# Tomashevich.net
KiCad netlist of a schematic drawn in Altium Designer
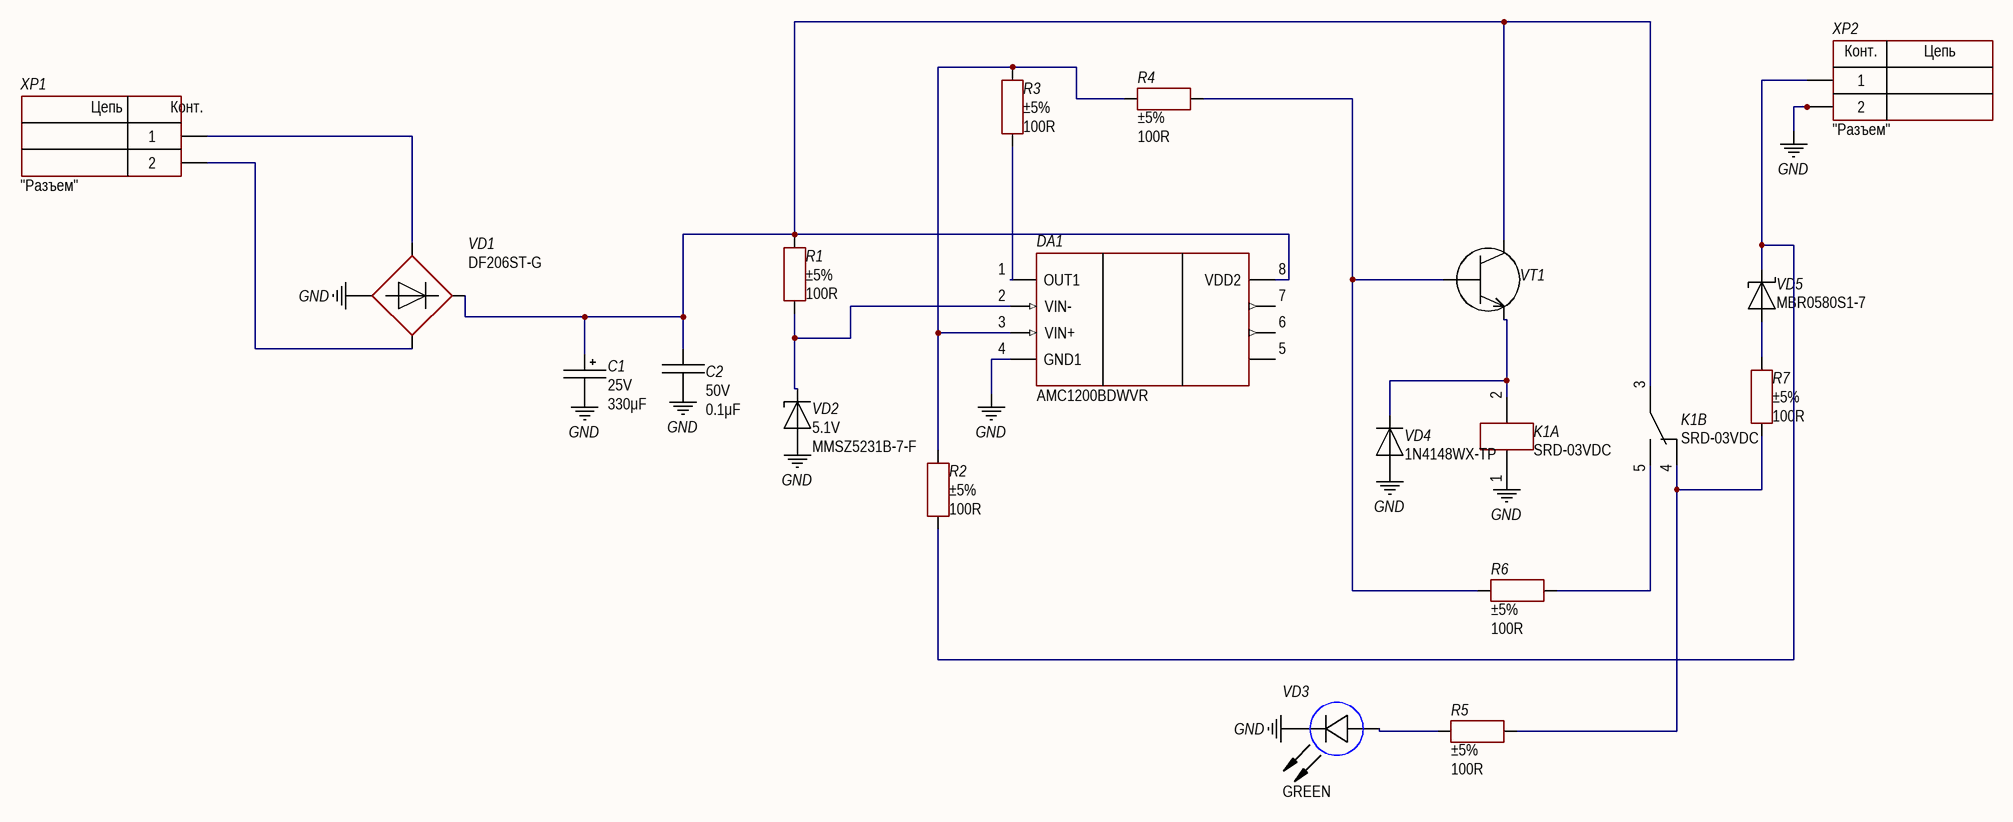
[diagram p0: Tomashevich.SchDoc]

(export (version "E")
  (design (tool "Eeschema 10.0.6"))
  (components
    (comp (ref "C1")
      (value "330μF")
      (footprint "CAP: D6.3C2.5H11")
      (fields
        (field (name "MANUFACTURER") "Wurth")
        (field (name "PARTNUMBER") "860080475013")
        (field (name "VALUEMANUFACTURERPARTNUMBER") "Aluminium capacitor, 330μF, 25V, ±20%, 54mOhm, 14x10x5 mm, -55...+105°C")
        (field (name "VOLTAGE") "25V")
      )
      (libsource (lib "capacitor") (part "Aluminium"))
    )
    (comp (ref "C2")
      (value "0.1μF")
      (footprint "CAP: 1206")
      (fields
        (field (name "MANUFACTURER") "Yageo")
        (field (name "PARTNUMBER") "CC1206KRX7R9BB104")
        (field (name "VALUEMANUFACTURERPARTNUMBER") "Ceramic capacitor, 0.1μF, X7R, ±10%, 50V, 1206, -55...+125°C")
        (field (name "VOLTAGE") "50V")
      )
      (libsource (lib "capacitor") (part "Ceramic_1206"))
    )
    (comp (ref "DA1")
      (value "~")
      (footprint "8-SOIC-W")
      (description "Isolator amplifier")
      (fields
        (field (name "MANUFACTURER") "Texas Instruments")
        (field (name "VALUEMANUFACTURERPARTNUMBER") "IC isolator amplifier, Differential, 100 kHz, 2.7...5.5V, -40...+105°C, 8-SOIC")
        (field (name "PARTNUMBER") "AMC1200BDWVR")
      )
      (libsource (lib "ic-amplifier") (part "AMC1200BDWVR"))
    )
    (comp (ref "K1")
      (value "~")
      (footprint "REL: SRD-03VDC")
      (fields
        (field (name "MANUFACTURER") "Ningbo Songle")
        (field (name "VALUEMANUFACTURERPARTNUMBER") "Electromechanics relay, 3VDC, 250VAC, 10A, 1NO, -40...+85°C")
        (field (name "PARTNUMBER") "SRD-03VDC")
      )
      (libsource (lib "") (part "Relay_SRD-03VDC_1"))
    )
    (comp (ref "R1")
      (value "100R")
      (footprint "RES: 1206")
      (fields
        (field (name "MANUFACTURER") "Yageo")
        (field (name "PARTNUMBER") "RC1206JR-07100RL")
        (field (name "VALUEMANUFACTURERPARTNUMBER") "Resistor film, 100R, ±5%, 1206, 0.25W, -55...+125°C")
        (field (name "TOLERANCE") "±5%")
      )
      (libsource (lib "resistor") (part "Resistor_1206"))
    )
    (comp (ref "R2")
      (value "100R")
      (footprint "RES: 1206")
      (fields
        (field (name "MANUFACTURER") "Yageo")
        (field (name "PARTNUMBER") "RC1206JR-07100RL")
        (field (name "VALUEMANUFACTURERPARTNUMBER") "Resistor film, 100R, ±5%, 1206, 0.25W, -55...+125°C")
        (field (name "TOLERANCE") "±5%")
      )
      (libsource (lib "resistor") (part "Resistor_1206"))
    )
    (comp (ref "R3")
      (value "100R")
      (footprint "RES: 1206")
      (fields
        (field (name "MANUFACTURER") "Yageo")
        (field (name "PARTNUMBER") "RC1206JR-07100RL")
        (field (name "VALUEMANUFACTURERPARTNUMBER") "Resistor film, 100R, ±5%, 1206, 0.25W, -55...+125°C")
        (field (name "TOLERANCE") "±5%")
      )
      (libsource (lib "resistor") (part "Resistor_1206"))
    )
    (comp (ref "R4")
      (value "100R")
      (footprint "RES: 1206")
      (fields
        (field (name "MANUFACTURER") "Yageo")
        (field (name "PARTNUMBER") "RC1206JR-07100RL")
        (field (name "VALUEMANUFACTURERPARTNUMBER") "Resistor film, 100R, ±5%, 1206, 0.25W, -55...+125°C")
        (field (name "TOLERANCE") "±5%")
      )
      (libsource (lib "") (part "Resistor_1206_2"))
    )
    (comp (ref "R5")
      (value "100R")
      (footprint "RES: 1206")
      (fields
        (field (name "MANUFACTURER") "Yageo")
        (field (name "PARTNUMBER") "RC1206JR-07100RL")
        (field (name "VALUEMANUFACTURERPARTNUMBER") "Resistor film, 100R, ±5%, 1206, 0.25W, -55...+125°C")
        (field (name "TOLERANCE") "±5%")
      )
      (libsource (lib "") (part "Resistor_1206_1"))
    )
    (comp (ref "R6")
      (value "100R")
      (footprint "RES: 1206")
      (fields
        (field (name "MANUFACTURER") "Yageo")
        (field (name "PARTNUMBER") "RC1206JR-07100RL")
        (field (name "VALUEMANUFACTURERPARTNUMBER") "Resistor film, 100R, ±5%, 1206, 0.25W, -55...+125°C")
        (field (name "TOLERANCE") "±5%")
      )
      (libsource (lib "") (part "Resistor_1206_1"))
    )
    (comp (ref "R7")
      (value "100R")
      (footprint "RES: 1206")
      (fields
        (field (name "MANUFACTURER") "Yageo")
        (field (name "PARTNUMBER") "RC1206JR-07100RL")
        (field (name "VALUEMANUFACTURERPARTNUMBER") "Resistor film, 100R, ±5%, 1206, 0.25W, -55...+125°C")
        (field (name "TOLERANCE") "±5%")
      )
      (libsource (lib "resistor") (part "Resistor_1206"))
    )
    (comp (ref "VD1")
      (value "~")
      (footprint "DIODE: CD-MBL2")
      (fields
        (field (name "MANUFACTURER") "Comchip Technology")
        (field (name "VALUEMANUFACTURERPARTNUMBER") "Single phase rectifier, 600V, 2A, 1.1V, 4-SMD, -55...+150°C")
        (field (name "VOLTAGE") "600V")
        (field (name "PARTNUMBER") "DF206ST-G")
      )
      (libsource (lib "diode") (part "1PH rectifier"))
    )
    (comp (ref "VD2")
      (value "~")
      (footprint "DIODE: SMA")
      (fields
        (field (name "MANUFACTURER") "Diodes Incorporated")
        (field (name "VALUEMANUFACTURERPARTNUMBER") "Zener diode, 5.1V, 500mW, 0.9V, 17Ohm, SOD-123, -55...+150°C")
        (field (name "VOLTAGE") "5.1V")
        (field (name "PARTNUMBER") "MMSZ5231B-7-F")
      )
      (libsource (lib "diode") (part "Zener_single"))
    )
    (comp (ref "VD3")
      (value "~")
      (footprint "LED: 1206G")
      (fields
        (field (name "VALUEMANUFACTURERPARTNUMBER") "LED, Green, *, *, *, -55...+150°C")
        (field (name "COLOR") "GREEN")
      )
      (libsource (lib "diode") (part "LED_single"))
    )
    (comp (ref "VD4")
      (value "~")
      (footprint "DIODE: SMA")
      (fields
        (field (name "MANUFACTURER") "Micro Commercial")
        (field (name "VALUEMANUFACTURERPARTNUMBER") "Single diode, 75V, 150mA, 1V, 4ns, SOD-323, -55...+150°C")
        (field (name "VOLTAGE") "75V")
        (field (name "PARTNUMBER") "1N4148WX-TP")
      )
      (libsource (lib "diode") (part "Diode_single"))
    )
    (comp (ref "VD5")
      (value "~")
      (footprint "DIODE: SMA")
      (fields
        (field (name "MANUFACTURER") "Diodes Incorporated")
        (field (name "VALUEMANUFACTURERPARTNUMBER") "Schottky diode, 80V, 500mA, 1V, 15pF, SOD-123, -55...+150°C")
        (field (name "VOLTAGE") "80V")
        (field (name "PARTNUMBER") "MBR0580S1-7")
      )
      (libsource (lib "diode") (part "Schottky_single"))
    )
    (comp (ref "VT1")
      (value "transistor")
      (footprint "TO247")
      (libsource (lib "Schlib1") (part "transistor"))
    )
    (comp (ref "XP1")
      (value "~")
      (footprint "CON: DG350-3.5-02P")
      (fields
        (field (name "MANUFACTURER") "Degson")
        (field (name "VALUEMANUFACTURERPARTNUMBER") "Terminal connector, 2pin, 3.5mm, 300VAC, 10A")
        (field (name "PARTNUMBER") "DG350-3.5-02P-14")
        (field (name "COMMENTTEXT") "\"Разъем\"")
      )
      (libsource (lib "connector") (part "Connector_terminal_2pin"))
    )
    (comp (ref "XP2")
      (value "~")
      (footprint "CON: DG350-3.5-02P")
      (fields
        (field (name "MANUFACTURER") "Degson")
        (field (name "VALUEMANUFACTURERPARTNUMBER") "Terminal connector, 2pin, 3.5mm, 300VAC, 10A")
        (field (name "PARTNUMBER") "DG350-3.5-02P-14")
        (field (name "COMMENTTEXT") "\"Разъем\"")
      )
      (libsource (lib "") (part "Connector_terminal_2pin_1"))
    )
  )
  (nets
    (net (code "1") (name "GND") (class "Default")
      (node (ref "C1") (pin "2") (pinfunction "2_2") (pintype "passive"))
      (node (ref "C2") (pin "1") (pinfunction "1_1") (pintype "passive"))
      (node (ref "DA1") (pin "4") (pinfunction "GND1_4") (pintype "power_in"))
      (node (ref "K1") (pin "1") (pinfunction "1_1") (pintype "passive"))
      (node (ref "VD1") (pin "1") (pinfunction "1_1") (pintype "passive"))
      (node (ref "VD2") (pin "1") (pinfunction "A_1") (pintype "passive"))
      (node (ref "VD3") (pin "2") (pinfunction "C_2") (pintype "passive"))
      (node (ref "VD4") (pin "1") (pinfunction "1_1") (pintype "passive"))
      (node (ref "XP2") (pin "2") (pinfunction "2_2") (pintype "passive"))
    )
    (net (code "2") (name "Net-(DA1-OUT1)") (class "Default")
      (node (ref "DA1") (pin "1") (pinfunction "OUT1_1") (pintype "power_in"))
      (node (ref "R3") (pin "1") (pinfunction "1_1") (pintype "passive"))
    )
    (net (code "3") (name "Net-(DA1-VDD2)") (class "Default")
      (node (ref "C1") (pin "1") (pinfunction "1_1") (pintype "passive"))
      (node (ref "C2") (pin "2") (pinfunction "2_2") (pintype "passive"))
      (node (ref "DA1") (pin "8") (pinfunction "VDD2_8") (pintype "power_in"))
      (node (ref "K1") (pin "3") (pinfunction "3_3") (pintype "passive"))
      (node (ref "R1") (pin "2") (pinfunction "2_2") (pintype "passive"))
      (node (ref "VD1") (pin "3") (pinfunction "3_3") (pintype "passive"))
      (node (ref "VT1") (pin "3") (pinfunction "3_3") (pintype "passive"))
    )
    (net (code "4") (name "Net-(DA1-VIN+)") (class "Default")
      (node (ref "DA1") (pin "3") (pinfunction "VIN+_3") (pintype "input"))
      (node (ref "R2") (pin "2") (pinfunction "2_2") (pintype "passive"))
      (node (ref "R3") (pin "2") (pinfunction "2_2") (pintype "passive"))
      (node (ref "R4") (pin "2") (pinfunction "2_2") (pintype "passive"))
    )
    (net (code "5") (name "Net-(DA1-VIN-)") (class "Default")
      (node (ref "DA1") (pin "2") (pinfunction "VIN-_2") (pintype "input"))
      (node (ref "R1") (pin "1") (pinfunction "1_1") (pintype "passive"))
      (node (ref "VD2") (pin "2") (pinfunction "C_2") (pintype "passive"))
    )
    (net (code "6") (name "Net-(K1-Pad2)") (class "Default")
      (node (ref "K1") (pin "2") (pinfunction "2_2") (pintype "passive"))
      (node (ref "VD4") (pin "2") (pinfunction "2_2") (pintype "passive"))
      (node (ref "VT1") (pin "2") (pinfunction "2_2") (pintype "passive"))
    )
    (net (code "7") (name "Net-(K1-Pad4)") (class "Default")
      (node (ref "K1") (pin "4") (pinfunction "4_4") (pintype "passive"))
      (node (ref "R5") (pin "1") (pinfunction "1_1") (pintype "passive"))
      (node (ref "R7") (pin "1") (pinfunction "1_1") (pintype "passive"))
    )
    (net (code "8") (name "Net-(K1-Pad5)") (class "Default")
      (node (ref "K1") (pin "5") (pinfunction "5_5") (pintype "passive"))
      (node (ref "R6") (pin "1") (pinfunction "1_1") (pintype "passive"))
    )
    (net (code "9") (name "Net-(R2-Pad1)") (class "Default")
      (node (ref "R2") (pin "1") (pinfunction "1_1") (pintype "passive"))
      (node (ref "VD5") (pin "2") (pinfunction "2_2") (pintype "passive"))
      (node (ref "XP2") (pin "1") (pinfunction "1_1") (pintype "passive"))
    )
    (net (code "10") (name "Net-(R4-Pad1)") (class "Default")
      (node (ref "R4") (pin "1") (pinfunction "1_1") (pintype "passive"))
      (node (ref "R6") (pin "2") (pinfunction "2_2") (pintype "passive"))
      (node (ref "VT1") (pin "1") (pinfunction "1_1") (pintype "passive"))
    )
    (net (code "11") (name "Net-(R7-Pad2)") (class "Default")
      (node (ref "R7") (pin "2") (pinfunction "2_2") (pintype "passive"))
      (node (ref "VD5") (pin "1") (pinfunction "1_1") (pintype "passive"))
    )
    (net (code "12") (name "Net-(VD1-Pad2)") (class "Default")
      (node (ref "VD1") (pin "2") (pinfunction "2_2") (pintype "passive"))
      (node (ref "XP1") (pin "1") (pinfunction "1_1") (pintype "passive"))
    )
    (net (code "13") (name "Net-(VD1-Pad4)") (class "Default")
      (node (ref "VD1") (pin "4") (pinfunction "4_4") (pintype "passive"))
      (node (ref "XP1") (pin "2") (pinfunction "2_2") (pintype "passive"))
    )
    (net (code "14") (name "Net-(VD3-A)") (class "Default")
      (node (ref "R5") (pin "2") (pinfunction "2_2") (pintype "passive"))
      (node (ref "VD3") (pin "1") (pinfunction "A_1") (pintype "passive"))
    )
    (net (code "15") (name "unconnected-(DA1-Pad5)") (class "Default")
      (node (ref "DA1") (pin "5") (pintype "power_in"))
    )
    (net (code "16") (name "unconnected-(DA1-Pad6)") (class "Default")
      (node (ref "DA1") (pin "6") (pintype "output"))
    )
    (net (code "17") (name "unconnected-(DA1-Pad7)") (class "Default")
      (node (ref "DA1") (pin "7") (pintype "output"))
    )
  )
)
